# driver.net
KiCad netlist of a schematic drawn in Altium Designer
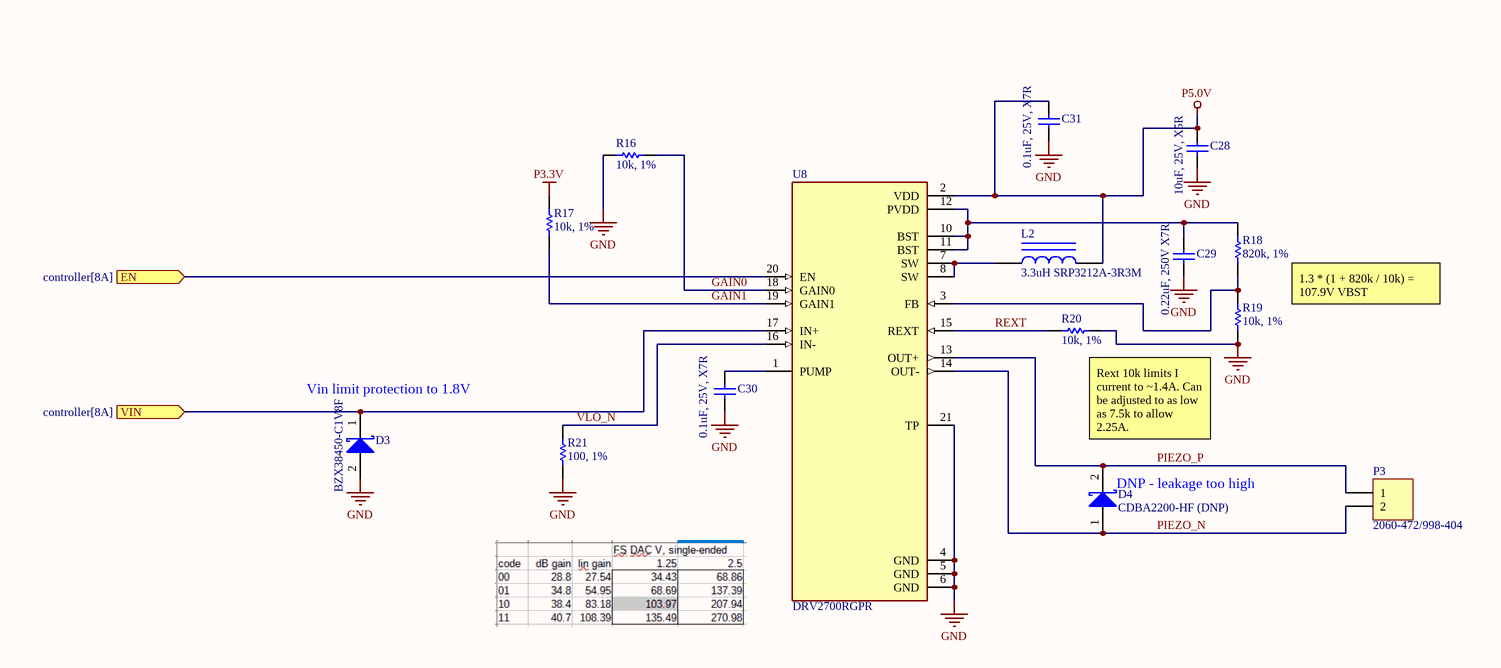
[diagram p0: driver.SchDoc]

(export (version "E")
  (design (tool "Eeschema 10.0.6"))
  (components
    (comp (ref "C28")
      (value "10uF, 25V, X5R")
      (footprint "B_CAP0805")
      (description "Capacitor (Semiconductor SIM Model)")
      (fields (field (name "MPN") "GRM21BR61E106KA73L"))
      (libsource (lib "Miscellaneous Devices") (part "Cap Semi"))
    )
    (comp (ref "C29")
      (value "0.22uF, 250V X7R")
      (footprint "B_CAP1210")
      (description "Capacitor (Semiconductor SIM Model)")
      (fields (field (name "MPN") "GCJ32DR72E224KXJ1L"))
      (libsource (lib "Miscellaneous Devices") (part "Cap Semi"))
    )
    (comp (ref "C30")
      (value "0.1uF, 25V, X7R")
      (footprint "B_CAP0603")
      (description "Capacitor (Semiconductor SIM Model)")
      (fields (field (name "MPN") "CC0603KRX7R8BB104"))
      (libsource (lib "Miscellaneous Devices") (part "Cap Semi"))
    )
    (comp (ref "C31")
      (value "0.1uF, 25V, X7R")
      (footprint "B_CAP0603")
      (description "Capacitor (Semiconductor SIM Model)")
      (fields (field (name "MPN") "CC0603KRX7R8BB104"))
      (libsource (lib "Miscellaneous Devices") (part "Cap Semi"))
    )
    (comp (ref "D3")
      (value "BZX38450-C1V8F")
      (footprint "SOD-323")
      (description "Schottky Diode")
      (libsource (lib "Miscellaneous Devices") (part "D Schottky"))
    )
    (comp (ref "D4")
      (value "CDBA2200-HF (DNP)")
      (footprint "DSO-C2/X1.8")
      (description "Schottky Diode")
      (fields (field (name "MPN") "DNP"))
      (libsource (lib "") (part "D Schottky_1"))
    )
    (comp (ref "L2")
      (value "3.3uH SRP3212A-3R3M")
      (footprint "B_IND1210_BOURNES")
      (description "Magnetic-Core Inductor")
      (fields (field (name "MPN") "SRP3212A-3R3M"))
      (libsource (lib "Miscellaneous Devices") (part "Inductor Iron"))
    )
    (comp (ref "P3")
      (value "2060-472/998-404")
      (footprint "WAGO_2060-472/998-404")
      (description "Header, 2-Pin")
      (fields (field (name "PUBLISHER") "Altium Limited"))
      (libsource (lib "Miscellaneous Connectors") (part "Header 2"))
    )
    (comp (ref "R16")
      (value "10k, 1%")
      (footprint "B_RES0603")
      (description "Resistor")
      (fields (field (name "MPN") "RC0603FR-0710KL"))
      (libsource (lib "Miscellaneous Devices") (part "Res1"))
    )
    (comp (ref "R17")
      (value "10k, 1%")
      (footprint "B_RES0603")
      (description "Resistor")
      (fields (field (name "MPN") "RC0603FR-0710KL"))
      (libsource (lib "Miscellaneous Devices") (part "Res1"))
    )
    (comp (ref "R18")
      (value "820k, 1%")
      (footprint "B_RES0603")
      (description "Resistor")
      (fields (field (name "MPN") "RC0603FR-07820KL"))
      (libsource (lib "Miscellaneous Devices") (part "Res1"))
    )
    (comp (ref "R19")
      (value "10k, 1%")
      (footprint "B_RES0603")
      (description "Resistor")
      (fields (field (name "MPN") "RC0603FR-0710KL"))
      (libsource (lib "Miscellaneous Devices") (part "Res1"))
    )
    (comp (ref "R20")
      (value "10k, 1%")
      (footprint "B_RES0603")
      (description "Resistor")
      (fields (field (name "MPN") "RC0603FR-0710KL"))
      (libsource (lib "Miscellaneous Devices") (part "Res1"))
    )
    (comp (ref "R21")
      (value "100, 1%")
      (footprint "B_RES0603")
      (description "Resistor")
      (fields (field (name "MPN") "ANY"))
      (libsource (lib "Miscellaneous Devices") (part "Res1"))
    )
    (comp (ref "U8")
      (value "DRV2700RGPR")
      (footprint "QFN50P400X400X100_HS-21N_DRV2700")
      (description "Motor Driver Analog 20-QFN _4x4_")
      (fields (field (name "MF") "Texas Instruments") (field (name "MPN") "DRV2700RGP(T/R)"))
      (libsource (lib "DRV2700RGPR") (part "DRV2700RGPR"))
    )
  )
  (nets
    (net (code "1") (name "/EN") (class "Default")
      (node (ref "U8") (pin "20") (pinfunction "EN_20") (pintype "input"))
    )
    (net (code "2") (name "/GAIN0") (class "Default")
      (node (ref "R16") (pin "1") (pinfunction "1_1") (pintype "passive"))
      (node (ref "U8") (pin "18") (pinfunction "GAIN0_18") (pintype "input"))
    )
    (net (code "3") (name "/GAIN1") (class "Default")
      (node (ref "R17") (pin "2") (pinfunction "2_2") (pintype "passive"))
      (node (ref "U8") (pin "19") (pinfunction "GAIN1_19") (pintype "input"))
    )
    (net (code "4") (name "/PIEZO_N") (class "Default")
      (node (ref "D4") (pin "1") (pinfunction "A_1") (pintype "passive"))
      (node (ref "P3") (pin "2") (pinfunction "2_2") (pintype "passive"))
      (node (ref "U8") (pin "14") (pinfunction "OUT-_14") (pintype "output"))
    )
    (net (code "5") (name "/PIEZO_P") (class "Default")
      (node (ref "D4") (pin "2") (pinfunction "K_2") (pintype "passive"))
      (node (ref "P3") (pin "1") (pinfunction "1_1") (pintype "passive"))
      (node (ref "U8") (pin "13") (pinfunction "OUT+_13") (pintype "output"))
    )
    (net (code "6") (name "/REXT") (class "Default")
      (node (ref "R20") (pin "1") (pinfunction "1_1") (pintype "passive"))
      (node (ref "U8") (pin "15") (pinfunction "REXT_15") (pintype "input"))
    )
    (net (code "7") (name "/VIN") (class "Default")
      (node (ref "D3") (pin "1") (pinfunction "K_1") (pintype "passive"))
      (node (ref "U8") (pin "17") (pinfunction "IN+_17") (pintype "input"))
    )
    (net (code "8") (name "/VLO_N") (class "Default")
      (node (ref "R21") (pin "1") (pinfunction "1_1") (pintype "passive"))
      (node (ref "U8") (pin "16") (pinfunction "IN-_16") (pintype "input"))
    )
    (net (code "9") (name "GND") (class "Default")
      (node (ref "C28") (pin "2") (pinfunction "2_2") (pintype "passive"))
      (node (ref "C29") (pin "2") (pinfunction "2_2") (pintype "passive"))
      (node (ref "C30") (pin "2") (pinfunction "2_2") (pintype "passive"))
      (node (ref "C31") (pin "2") (pinfunction "2_2") (pintype "passive"))
      (node (ref "D3") (pin "2") (pinfunction "A_2") (pintype "passive"))
      (node (ref "R16") (pin "2") (pinfunction "2_2") (pintype "passive"))
      (node (ref "R19") (pin "1") (pinfunction "1_1") (pintype "passive"))
      (node (ref "R20") (pin "2") (pinfunction "2_2") (pintype "passive"))
      (node (ref "R21") (pin "2") (pinfunction "2_2") (pintype "passive"))
      (node (ref "U8") (pin "21") (pinfunction "TP_21") (pintype "power_in"))
      (node (ref "U8") (pin "4") (pinfunction "GND_4") (pintype "power_in"))
      (node (ref "U8") (pin "5") (pinfunction "GND_5") (pintype "power_in"))
      (node (ref "U8") (pin "6") (pinfunction "GND_6") (pintype "power_in"))
    )
    (net (code "10") (name "Net-(L2-Pad1)") (class "Default")
      (node (ref "L2") (pin "1") (pinfunction "1_1") (pintype "passive"))
      (node (ref "U8") (pin "7") (pinfunction "SW_7") (pintype "passive"))
      (node (ref "U8") (pin "8") (pinfunction "SW_8") (pintype "passive"))
    )
    (net (code "11") (name "Net-(U8-FB)") (class "Default")
      (node (ref "R18") (pin "1") (pinfunction "1_1") (pintype "passive"))
      (node (ref "R19") (pin "2") (pinfunction "2_2") (pintype "passive"))
      (node (ref "U8") (pin "3") (pinfunction "FB_3") (pintype "input"))
    )
    (net (code "12") (name "Net-(U8-PUMP)") (class "Default")
      (node (ref "C30") (pin "1") (pinfunction "1_1") (pintype "passive"))
      (node (ref "U8") (pin "1") (pinfunction "PUMP_1") (pintype "passive"))
    )
    (net (code "13") (name "Net-(U8-PVDD)") (class "Default")
      (node (ref "C29") (pin "1") (pinfunction "1_1") (pintype "passive"))
      (node (ref "R18") (pin "2") (pinfunction "2_2") (pintype "passive"))
      (node (ref "U8") (pin "10") (pinfunction "BST_10") (pintype "power_in"))
      (node (ref "U8") (pin "11") (pinfunction "BST_11") (pintype "power_in"))
      (node (ref "U8") (pin "12") (pinfunction "PVDD_12") (pintype "power_in"))
    )
    (net (code "14") (name "P3.3V") (class "Default")
      (node (ref "R17") (pin "1") (pinfunction "1_1") (pintype "passive"))
    )
    (net (code "15") (name "P5.0V") (class "Default")
      (node (ref "C28") (pin "1") (pinfunction "1_1") (pintype "passive"))
      (node (ref "C31") (pin "1") (pinfunction "1_1") (pintype "passive"))
      (node (ref "L2") (pin "2") (pinfunction "2_2") (pintype "passive"))
      (node (ref "U8") (pin "2") (pinfunction "VDD_2") (pintype "power_in"))
    )
  )
)
